# Digital_Inputs.net
KiCad netlist of a schematic drawn in Altium Designer
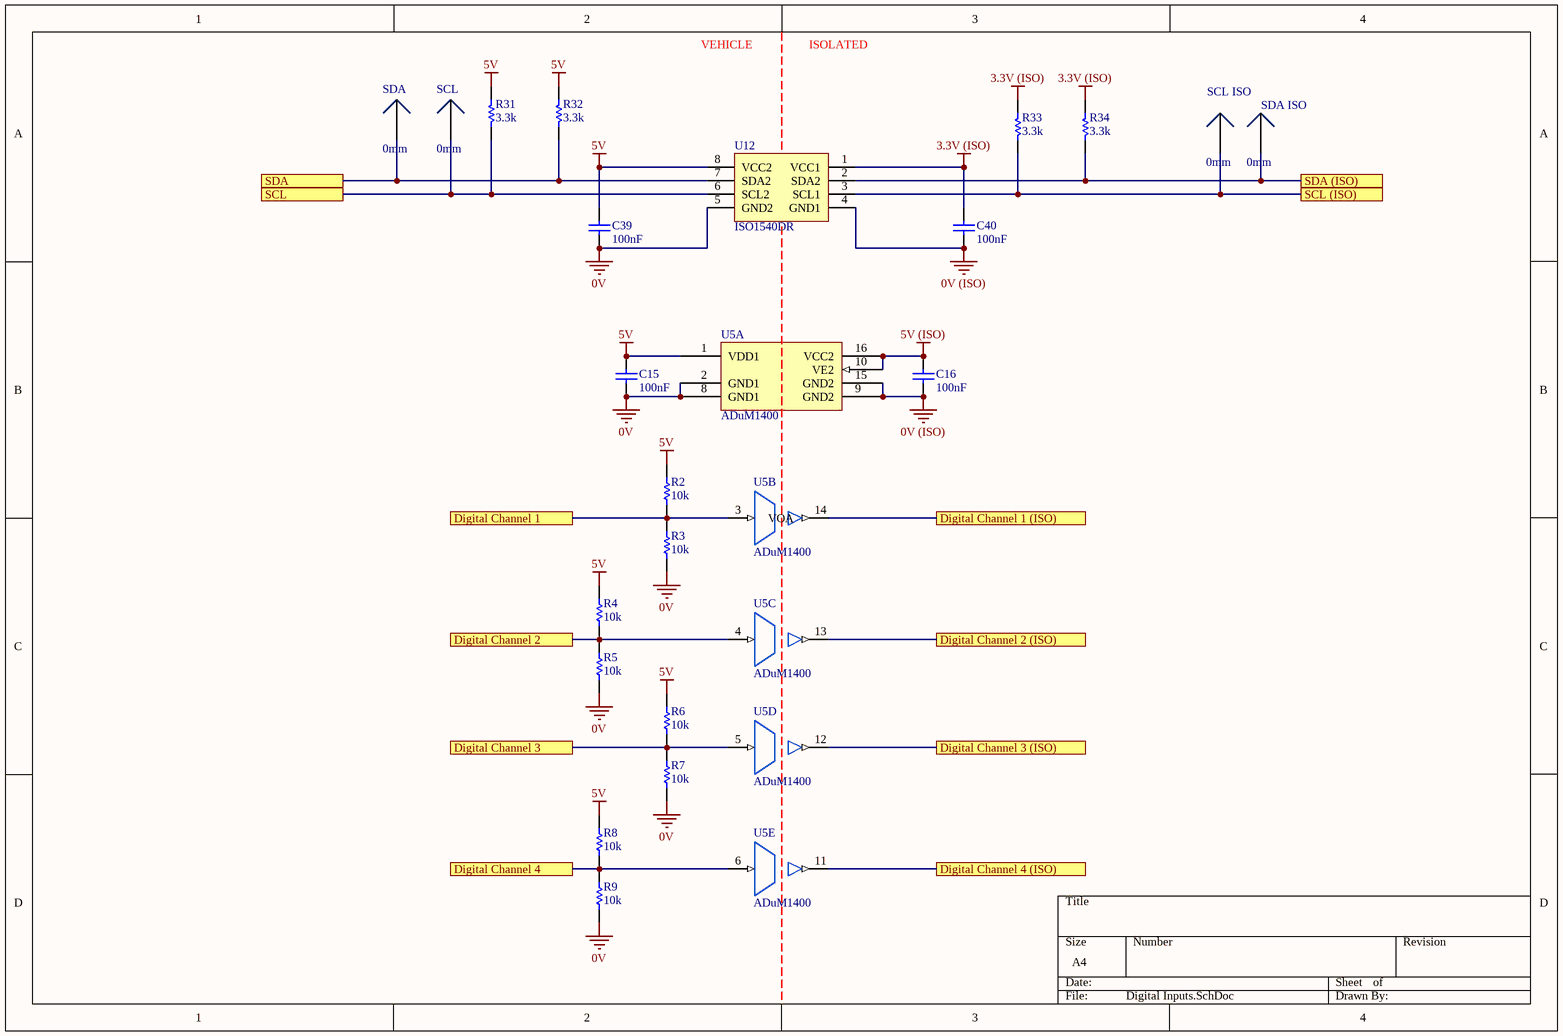
[diagram p0: Digital Inputs.SchDoc]

(export (version "E")
  (design (tool "Eeschema 10.0.6"))
  (components
    (comp (ref "C15")
      (value "100nF")
      (footprint "0805")
      (fields
        (field (name "PART NUMBER") "GCM21BR71E104KA37L")
        (field (name "TOLERANCE") "10%")
        (field (name "MANUFACTURER") "muRata")
      )
      (libsource (lib "ts_20-standard-library") (part "Capacitor"))
    )
    (comp (ref "C16")
      (value "100nF")
      (footprint "0805")
      (fields
        (field (name "PART NUMBER") "GCM21BR71E104KA37L")
        (field (name "TOLERANCE") "10%")
        (field (name "MANUFACTURER") "muRata")
      )
      (libsource (lib "ts_20-standard-library") (part "Capacitor"))
    )
    (comp (ref "C39")
      (value "100nF")
      (footprint "0805")
      (fields
        (field (name "PART NUMBER") "GCM21BR71E104KA37L")
        (field (name "TOLERANCE") "10%")
        (field (name "MANUFACTURER") "muRata")
      )
      (libsource (lib "ts_20-standard-library") (part "Capacitor"))
    )
    (comp (ref "C40")
      (value "100nF")
      (footprint "0805")
      (fields
        (field (name "PART NUMBER") "GCM21BR71E104KA37L")
        (field (name "TOLERANCE") "10%")
        (field (name "MANUFACTURER") "muRata")
      )
      (libsource (lib "ts_20-standard-library") (part "Capacitor"))
    )
    (comp (ref "R2")
      (value "10k")
      (footprint "0805")
      (fields
        (field (name "PART NUMBER") "RC0805FR0710KL")
        (field (name "MANUFACTURER") "YAGEO")
        (field (name "TOLERANCE") "0.01")
      )
      (libsource (lib "ts_20-standard-library") (part "Resistor"))
    )
    (comp (ref "R3")
      (value "10k")
      (footprint "0805")
      (fields
        (field (name "PART NUMBER") "RC0805FR0710KL")
        (field (name "MANUFACTURER") "YAGEO")
        (field (name "TOLERANCE") "0.01")
      )
      (libsource (lib "ts_20-standard-library") (part "Resistor"))
    )
    (comp (ref "R4")
      (value "10k")
      (footprint "0805")
      (fields
        (field (name "PART NUMBER") "RC0805FR0710KL")
        (field (name "MANUFACTURER") "YAGEO")
        (field (name "TOLERANCE") "0.01")
      )
      (libsource (lib "ts_20-standard-library") (part "Resistor"))
    )
    (comp (ref "R5")
      (value "10k")
      (footprint "0805")
      (fields
        (field (name "PART NUMBER") "RC0805FR0710KL")
        (field (name "MANUFACTURER") "YAGEO")
        (field (name "TOLERANCE") "0.01")
      )
      (libsource (lib "ts_20-standard-library") (part "Resistor"))
    )
    (comp (ref "R6")
      (value "10k")
      (footprint "0805")
      (fields
        (field (name "PART NUMBER") "RC0805FR0710KL")
        (field (name "MANUFACTURER") "YAGEO")
        (field (name "TOLERANCE") "0.01")
      )
      (libsource (lib "ts_20-standard-library") (part "Resistor"))
    )
    (comp (ref "R7")
      (value "10k")
      (footprint "0805")
      (fields
        (field (name "PART NUMBER") "RC0805FR0710KL")
        (field (name "MANUFACTURER") "YAGEO")
        (field (name "TOLERANCE") "0.01")
      )
      (libsource (lib "ts_20-standard-library") (part "Resistor"))
    )
    (comp (ref "R8")
      (value "10k")
      (footprint "0805")
      (fields
        (field (name "PART NUMBER") "RC0805FR0710KL")
        (field (name "MANUFACTURER") "YAGEO")
        (field (name "TOLERANCE") "0.01")
      )
      (libsource (lib "ts_20-standard-library") (part "Resistor"))
    )
    (comp (ref "R9")
      (value "10k")
      (footprint "0805")
      (fields
        (field (name "PART NUMBER") "RC0805FR0710KL")
        (field (name "MANUFACTURER") "YAGEO")
        (field (name "TOLERANCE") "0.01")
      )
      (libsource (lib "ts_20-standard-library") (part "Resistor"))
    )
    (comp (ref "R31")
      (value "3.3k")
      (footprint "0805")
      (fields
        (field (name "PART NUMBER") "RC0805FR073K3L")
        (field (name "MANUFACTURER") "YAGEO")
        (field (name "TOLERANCE") "0.01")
      )
      (libsource (lib "ts_20-standard-library") (part "Resistor"))
    )
    (comp (ref "R32")
      (value "3.3k")
      (footprint "0805")
      (fields
        (field (name "PART NUMBER") "RC0805FR073K3L")
        (field (name "MANUFACTURER") "YAGEO")
        (field (name "TOLERANCE") "0.01")
      )
      (libsource (lib "ts_20-standard-library") (part "Resistor"))
    )
    (comp (ref "R33")
      (value "3.3k")
      (footprint "0805")
      (fields
        (field (name "PART NUMBER") "RC0805FR073K3L")
        (field (name "MANUFACTURER") "YAGEO")
        (field (name "TOLERANCE") "0.01")
      )
      (libsource (lib "ts_20-standard-library") (part "Resistor"))
    )
    (comp (ref "R34")
      (value "3.3k")
      (footprint "0805")
      (fields
        (field (name "PART NUMBER") "RC0805FR073K3L")
        (field (name "MANUFACTURER") "YAGEO")
        (field (name "TOLERANCE") "0.01")
      )
      (libsource (lib "ts_20-standard-library") (part "Resistor"))
    )
    (comp (ref "SCL")
      (value "0mm")
      (footprint "SMD Test Point")
      (fields (field (name "PART NUMBER") "SMD Test Point") (field (name "CONTACT") "NA"))
      (libsource (lib "ts_20-standard-connectors") (part "Test Point"))
    )
    (comp (ref "SCL ISO")
      (value "0mm")
      (footprint "SMD Test Point")
      (fields (field (name "PART NUMBER") "SMD Test Point") (field (name "CONTACT") "NA"))
      (libsource (lib "ts_20-standard-connectors") (part "Test Point"))
    )
    (comp (ref "SDA")
      (value "0mm")
      (footprint "SMD Test Point")
      (fields (field (name "PART NUMBER") "SMD Test Point") (field (name "CONTACT") "NA"))
      (libsource (lib "ts_20-standard-connectors") (part "Test Point"))
    )
    (comp (ref "SDA ISO")
      (value "0mm")
      (footprint "SMD Test Point")
      (fields (field (name "PART NUMBER") "SMD Test Point") (field (name "CONTACT") "NA"))
      (libsource (lib "ts_20-standard-connectors") (part "Test Point"))
    )
    (comp (ref "U5")
      (value "ADuM1400")
      (footprint "AD 16-SOIC")
      (fields
        (field (name "MANUFACTURER") "Analog Devices")
        (field (name "DIGIKEY PART NUMBER") "ADUM1400WSRWZ-ND")
      )
      (libsource (lib "ts_20-standard-library") (part "ADuM1400"))
    )
    (comp (ref "U12")
      (value "ISO1540DR")
      (footprint "TI 8-SOIC")
      (description "I2C Digital Isolator (Multichannel)")
      (fields
        (field (name "MANUFACTURER") "Texas Instruments")
        (field (name "DIGIKEY PART NUMBER") "296-34871-1-ND")
      )
      (libsource (lib "ts_20-standard-library") (part "ISO1540DR"))
    )
  )
  (nets
    (net (code "1") (name "/Digital Channel 1") (class "Default")
      (node (ref "R2") (pin "1") (pinfunction "1_1") (pintype "passive"))
      (node (ref "R3") (pin "2") (pinfunction "2_2") (pintype "passive"))
      (node (ref "U5") (pin "3") (pinfunction "VIA_3") (pintype "input"))
    )
    (net (code "2") (name "/Digital Channel 1 (ISO)") (class "Default")
      (node (ref "U5") (pin "14") (pinfunction "VOA_14") (pintype "output"))
    )
    (net (code "3") (name "/Digital Channel 2") (class "Default")
      (node (ref "R4") (pin "1") (pinfunction "1_1") (pintype "passive"))
      (node (ref "R5") (pin "2") (pinfunction "2_2") (pintype "passive"))
      (node (ref "U5") (pin "4") (pinfunction "VIB_4") (pintype "input"))
    )
    (net (code "4") (name "/Digital Channel 2 (ISO)") (class "Default")
      (node (ref "U5") (pin "13") (pinfunction "VOB_13") (pintype "output"))
    )
    (net (code "5") (name "/Digital Channel 3") (class "Default")
      (node (ref "R6") (pin "1") (pinfunction "1_1") (pintype "passive"))
      (node (ref "R7") (pin "2") (pinfunction "2_2") (pintype "passive"))
      (node (ref "U5") (pin "5") (pinfunction "VIC_5") (pintype "input"))
    )
    (net (code "6") (name "/Digital Channel 3 (ISO)") (class "Default")
      (node (ref "U5") (pin "12") (pinfunction "VOC_12") (pintype "output"))
    )
    (net (code "7") (name "/Digital Channel 4") (class "Default")
      (node (ref "R8") (pin "1") (pinfunction "1_1") (pintype "passive"))
      (node (ref "R9") (pin "2") (pinfunction "2_2") (pintype "passive"))
      (node (ref "U5") (pin "6") (pinfunction "VID_6") (pintype "input"))
    )
    (net (code "8") (name "/Digital Channel 4 (ISO)") (class "Default")
      (node (ref "U5") (pin "11") (pinfunction "VOD_11") (pintype "output"))
    )
    (net (code "9") (name "/SCL") (class "Default")
      (node (ref "R31") (pin "1") (pinfunction "1_1") (pintype "passive"))
      (node (ref "SCL") (pin "1") (pinfunction "1_1") (pintype "passive"))
      (node (ref "U12") (pin "6") (pinfunction "SCL2_6") (pintype "power_in"))
    )
    (net (code "10") (name "/SCL (ISO)") (class "Default")
      (node (ref "R33") (pin "1") (pinfunction "1_1") (pintype "passive"))
      (node (ref "SCL ISO") (pin "1") (pinfunction "1_1") (pintype "passive"))
      (node (ref "U12") (pin "3") (pinfunction "SCL1_3") (pintype "power_in"))
    )
    (net (code "11") (name "/SDA") (class "Default")
      (node (ref "R32") (pin "1") (pinfunction "1_1") (pintype "passive"))
      (node (ref "SDA") (pin "1") (pinfunction "1_1") (pintype "passive"))
      (node (ref "U12") (pin "7") (pinfunction "SDA2_7") (pintype "power_in"))
    )
    (net (code "12") (name "/SDA (ISO)") (class "Default")
      (node (ref "R34") (pin "1") (pinfunction "1_1") (pintype "passive"))
      (node (ref "SDA ISO") (pin "1") (pinfunction "1_1") (pintype "passive"))
      (node (ref "U12") (pin "2") (pinfunction "SDA2_2") (pintype "power_in"))
    )
    (net (code "13") (name "0V") (class "Default")
      (node (ref "C15") (pin "1") (pinfunction "1_1") (pintype "passive"))
      (node (ref "C39") (pin "1") (pinfunction "1_1") (pintype "passive"))
      (node (ref "R3") (pin "1") (pinfunction "1_1") (pintype "passive"))
      (node (ref "R5") (pin "1") (pinfunction "1_1") (pintype "passive"))
      (node (ref "R7") (pin "1") (pinfunction "1_1") (pintype "passive"))
      (node (ref "R9") (pin "1") (pinfunction "1_1") (pintype "passive"))
      (node (ref "U12") (pin "5") (pinfunction "GND2_5") (pintype "power_in"))
      (node (ref "U5") (pin "2") (pinfunction "GND1_2") (pintype "power_in"))
      (node (ref "U5") (pin "8") (pinfunction "GND1_8") (pintype "power_in"))
    )
    (net (code "14") (name "0V (ISO)") (class "Default")
      (node (ref "C16") (pin "1") (pinfunction "1_1") (pintype "passive"))
      (node (ref "C40") (pin "1") (pinfunction "1_1") (pintype "passive"))
      (node (ref "U12") (pin "4") (pinfunction "GND1_4") (pintype "power_in"))
      (node (ref "U5") (pin "15") (pinfunction "GND2_15") (pintype "power_in"))
      (node (ref "U5") (pin "9") (pinfunction "GND2_9") (pintype "power_in"))
    )
    (net (code "15") (name "3.3V (ISO)") (class "Default")
      (node (ref "C40") (pin "2") (pinfunction "2_2") (pintype "passive"))
      (node (ref "R33") (pin "2") (pinfunction "2_2") (pintype "passive"))
      (node (ref "R34") (pin "2") (pinfunction "2_2") (pintype "passive"))
      (node (ref "U12") (pin "1") (pinfunction "VCC1_1") (pintype "power_in"))
    )
    (net (code "16") (name "5V") (class "Default")
      (node (ref "C15") (pin "2") (pinfunction "2_2") (pintype "passive"))
      (node (ref "C39") (pin "2") (pinfunction "2_2") (pintype "passive"))
      (node (ref "R2") (pin "2") (pinfunction "2_2") (pintype "passive"))
      (node (ref "R31") (pin "2") (pinfunction "2_2") (pintype "passive"))
      (node (ref "R32") (pin "2") (pinfunction "2_2") (pintype "passive"))
      (node (ref "R4") (pin "2") (pinfunction "2_2") (pintype "passive"))
      (node (ref "R6") (pin "2") (pinfunction "2_2") (pintype "passive"))
      (node (ref "R8") (pin "2") (pinfunction "2_2") (pintype "passive"))
      (node (ref "U12") (pin "8") (pinfunction "VCC2_8") (pintype "power_in"))
      (node (ref "U5") (pin "1") (pinfunction "VDD1_1") (pintype "power_in"))
    )
    (net (code "17") (name "5V (ISO)") (class "Default")
      (node (ref "C16") (pin "2") (pinfunction "2_2") (pintype "passive"))
      (node (ref "U5") (pin "10") (pinfunction "VE2_10") (pintype "input"))
      (node (ref "U5") (pin "16") (pinfunction "VCC2_16") (pintype "power_in"))
    )
  )
)
